# Kompressor_Steuerung.net
KiCad netlist of a schematic drawn in EAGLE
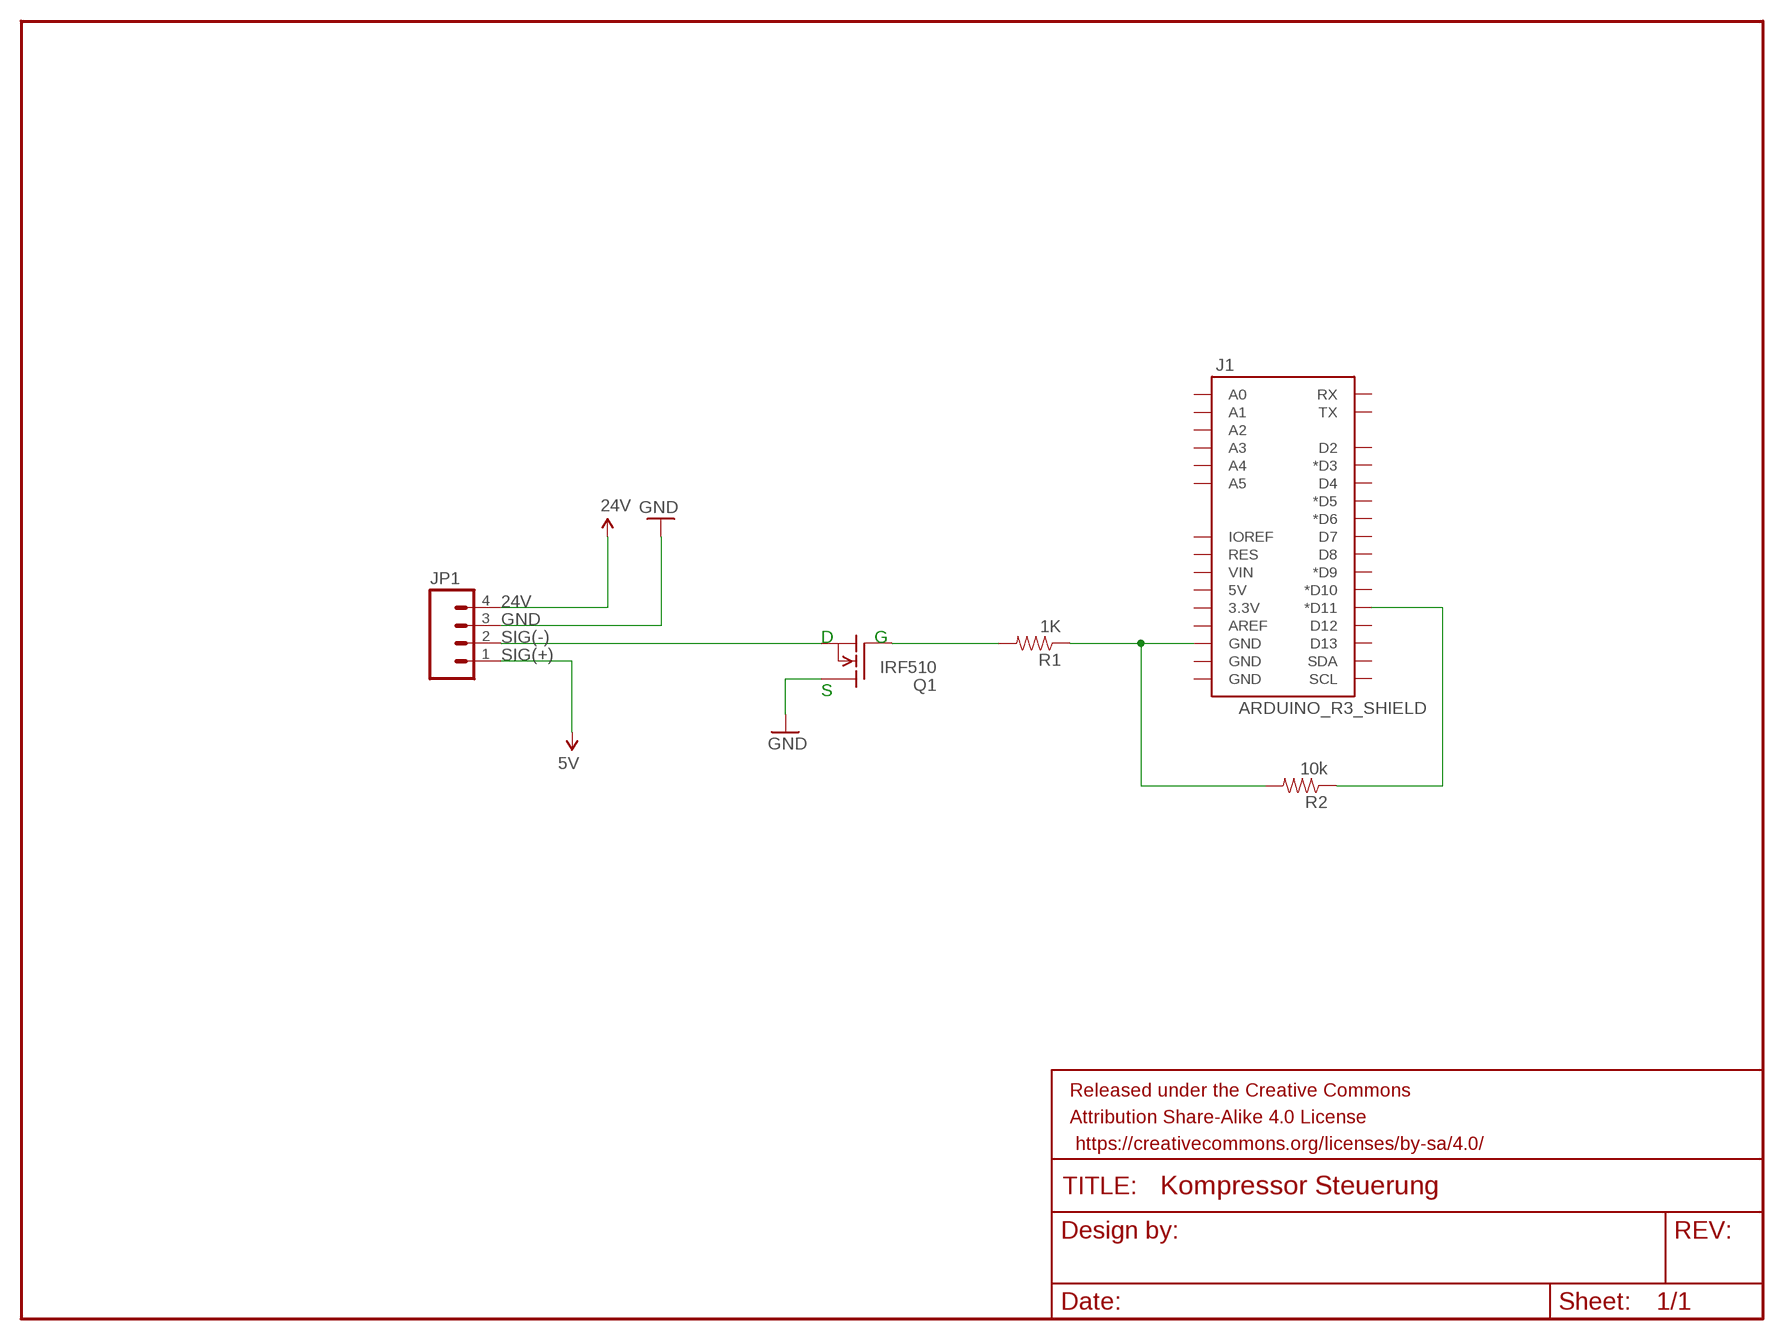
[diagram p0: schematic, sheet 1]

(export (version "E")
  (design (tool "Eeschema 10.0.6"))
  (components
    (comp (ref "FRAME1")
      (value "FRAME-LETTER")
      (footprint "eagle-import:CREATIVE_COMMONS")
      (fields (field (name "DESIGNER") "NAME"))
      (libsource (lib "eagle-import") (part "FRAME-LETTER"))
    )
    (comp (ref "J1")
      (value "ARDUINO_R3_SHIELD")
      (footprint "eagle-import:UNO_R3_SHIELD")
      (libsource (lib "eagle-import") (part "ARDUINO_R3_SHIELD"))
    )
    (comp (ref "JP1")
      (value "M04LOCK")
      (footprint "eagle-import:1X04_LOCK")
      (libsource (lib "eagle-import") (part "M04LOCK"))
    )
    (comp (ref "Q1")
      (value "IRF510")
      (footprint "eagle-import:TO220")
      (libsource (lib "eagle-import") (part "IRF510"))
    )
    (comp (ref "R1")
      (value "1K")
      (footprint "eagle-import:AXIAL-0.3")
      (libsource (lib "eagle-import") (part "1KOHM-1/4W-1%(PTH)"))
    )
    (comp (ref "R2")
      (value "10k")
      (footprint "eagle-import:AXIAL-0.3")
      (libsource (lib "eagle-import") (part "10KOHM-1/4W-1%(PTH)HORIZ"))
    )
  )
  (nets
    (net (code "1") (name "/SIG(-)") (class "Default")
      (node (ref "JP1") (pin "2") (pinfunction "2_2") (pintype "passive"))
      (node (ref "Q1") (pin "3") (pinfunction "S_3") (pintype "passive"))
    )
    (net (code "2") (name "5V") (class "Default")
      (node (ref "JP1") (pin "1") (pinfunction "1_1") (pintype "passive"))
    )
    (net (code "3") (name "24V") (class "Default")
      (node (ref "JP1") (pin "4") (pinfunction "4_4") (pintype "passive"))
    )
    (net (code "4") (name "GND") (class "Default")
      (node (ref "JP1") (pin "3") (pinfunction "3_3") (pintype "passive"))
      (node (ref "Q1") (pin "2") (pinfunction "D_2") (pintype "passive"))
    )
    (net (code "5") (name "Net-(J1-*D11)") (class "Default")
      (node (ref "J1") (pin "D11") (pinfunction "*D11_D11") (pintype "bidirectional"))
      (node (ref "R2") (pin "P$1") (pinfunction "1_P$1") (pintype "passive"))
    )
    (net (code "6") (name "Net-(Q1-G)") (class "Default")
      (node (ref "Q1") (pin "1") (pinfunction "G_1") (pintype "passive"))
      (node (ref "R1") (pin "P$2") (pinfunction "2_P$2") (pintype "passive"))
    )
    (net (code "7") (name "Net-(R1-1)") (class "Default")
      (node (ref "J1") (pin "GND@2") (pinfunction "GND_GND@2") (pintype "bidirectional"))
      (node (ref "R1") (pin "P$1") (pinfunction "1_P$1") (pintype "passive"))
      (node (ref "R2") (pin "P$2") (pinfunction "2_P$2") (pintype "passive"))
    )
    (net (code "8") (name "unconnected-(J1-*D3-PadD3)") (class "Default")
      (node (ref "J1") (pin "D3") (pinfunction "*D3_D3") (pintype "bidirectional"))
    )
    (net (code "9") (name "unconnected-(J1-*D5-PadD5)") (class "Default")
      (node (ref "J1") (pin "D5") (pinfunction "*D5_D5") (pintype "bidirectional"))
    )
    (net (code "10") (name "unconnected-(J1-*D6-PadD6)") (class "Default")
      (node (ref "J1") (pin "D6") (pinfunction "*D6_D6") (pintype "bidirectional"))
    )
    (net (code "11") (name "unconnected-(J1-*D9-PadD9)") (class "Default")
      (node (ref "J1") (pin "D9") (pinfunction "*D9_D9") (pintype "bidirectional"))
    )
    (net (code "12") (name "unconnected-(J1-*D10-PadD10)") (class "Default")
      (node (ref "J1") (pin "D10") (pinfunction "*D10_D10") (pintype "bidirectional"))
    )
    (net (code "13") (name "unconnected-(J1-GND-PadGND@0)") (class "Default")
      (node (ref "J1") (pin "GND@0") (pinfunction "GND_GND@0") (pintype "bidirectional"))
    )
    (net (code "14") (name "unconnected-(J1-GND-PadGND@1)") (class "Default")
      (node (ref "J1") (pin "GND@1") (pinfunction "GND_GND@1") (pintype "bidirectional"))
    )
    (net (code "15") (name "unconnected-(J1-Pad3.3V)") (class "Default")
      (node (ref "J1") (pin "3.3V") (pinfunction "3.3V_3.3V") (pintype "bidirectional"))
    )
    (net (code "16") (name "unconnected-(J1-Pad5V)") (class "Default")
      (node (ref "J1") (pin "5V") (pinfunction "5V_5V") (pintype "bidirectional"))
    )
    (net (code "17") (name "unconnected-(J1-PadA0)") (class "Default")
      (node (ref "J1") (pin "A0") (pinfunction "A0_A0") (pintype "bidirectional"))
    )
    (net (code "18") (name "unconnected-(J1-PadA1)") (class "Default")
      (node (ref "J1") (pin "A1") (pinfunction "A1_A1") (pintype "bidirectional"))
    )
    (net (code "19") (name "unconnected-(J1-PadA2)") (class "Default")
      (node (ref "J1") (pin "A2") (pinfunction "A2_A2") (pintype "bidirectional"))
    )
    (net (code "20") (name "unconnected-(J1-PadA3)") (class "Default")
      (node (ref "J1") (pin "A3") (pinfunction "A3_A3") (pintype "bidirectional"))
    )
    (net (code "21") (name "unconnected-(J1-PadA4)") (class "Default")
      (node (ref "J1") (pin "A4") (pinfunction "A4_A4") (pintype "bidirectional"))
    )
    (net (code "22") (name "unconnected-(J1-PadA5)") (class "Default")
      (node (ref "J1") (pin "A5") (pinfunction "A5_A5") (pintype "bidirectional"))
    )
    (net (code "23") (name "unconnected-(J1-PadAREF)") (class "Default")
      (node (ref "J1") (pin "AREF") (pinfunction "AREF_AREF") (pintype "bidirectional"))
    )
    (net (code "24") (name "unconnected-(J1-PadD2)") (class "Default")
      (node (ref "J1") (pin "D2") (pinfunction "D2_D2") (pintype "bidirectional"))
    )
    (net (code "25") (name "unconnected-(J1-PadD4)") (class "Default")
      (node (ref "J1") (pin "D4") (pinfunction "D4_D4") (pintype "bidirectional"))
    )
    (net (code "26") (name "unconnected-(J1-PadD7)") (class "Default")
      (node (ref "J1") (pin "D7") (pinfunction "D7_D7") (pintype "bidirectional"))
    )
    (net (code "27") (name "unconnected-(J1-PadD8)") (class "Default")
      (node (ref "J1") (pin "D8") (pinfunction "D8_D8") (pintype "bidirectional"))
    )
    (net (code "28") (name "unconnected-(J1-PadD12)") (class "Default")
      (node (ref "J1") (pin "D12") (pinfunction "D12_D12") (pintype "bidirectional"))
    )
    (net (code "29") (name "unconnected-(J1-PadD13)") (class "Default")
      (node (ref "J1") (pin "D13") (pinfunction "D13_D13") (pintype "bidirectional"))
    )
    (net (code "30") (name "unconnected-(J1-PadIOREF)") (class "Default")
      (node (ref "J1") (pin "IOREF") (pinfunction "IOREF_IOREF") (pintype "bidirectional"))
    )
    (net (code "31") (name "unconnected-(J1-PadRES)") (class "Default")
      (node (ref "J1") (pin "RES") (pinfunction "RES_RES") (pintype "bidirectional"))
    )
    (net (code "32") (name "unconnected-(J1-PadRX)") (class "Default")
      (node (ref "J1") (pin "RX") (pinfunction "RX_RX") (pintype "bidirectional"))
    )
    (net (code "33") (name "unconnected-(J1-PadSCL)") (class "Default")
      (node (ref "J1") (pin "SCL") (pinfunction "SCL_SCL") (pintype "bidirectional"))
    )
    (net (code "34") (name "unconnected-(J1-PadSDA)") (class "Default")
      (node (ref "J1") (pin "SDA") (pinfunction "SDA_SDA") (pintype "bidirectional"))
    )
    (net (code "35") (name "unconnected-(J1-PadTX)") (class "Default")
      (node (ref "J1") (pin "TX") (pinfunction "TX_TX") (pintype "bidirectional"))
    )
    (net (code "36") (name "unconnected-(J1-PadVIN)") (class "Default")
      (node (ref "J1") (pin "VIN") (pinfunction "VIN_VIN") (pintype "bidirectional"))
    )
  )
)
